# Teste.net
KiCad netlist of a schematic drawn in EAGLE
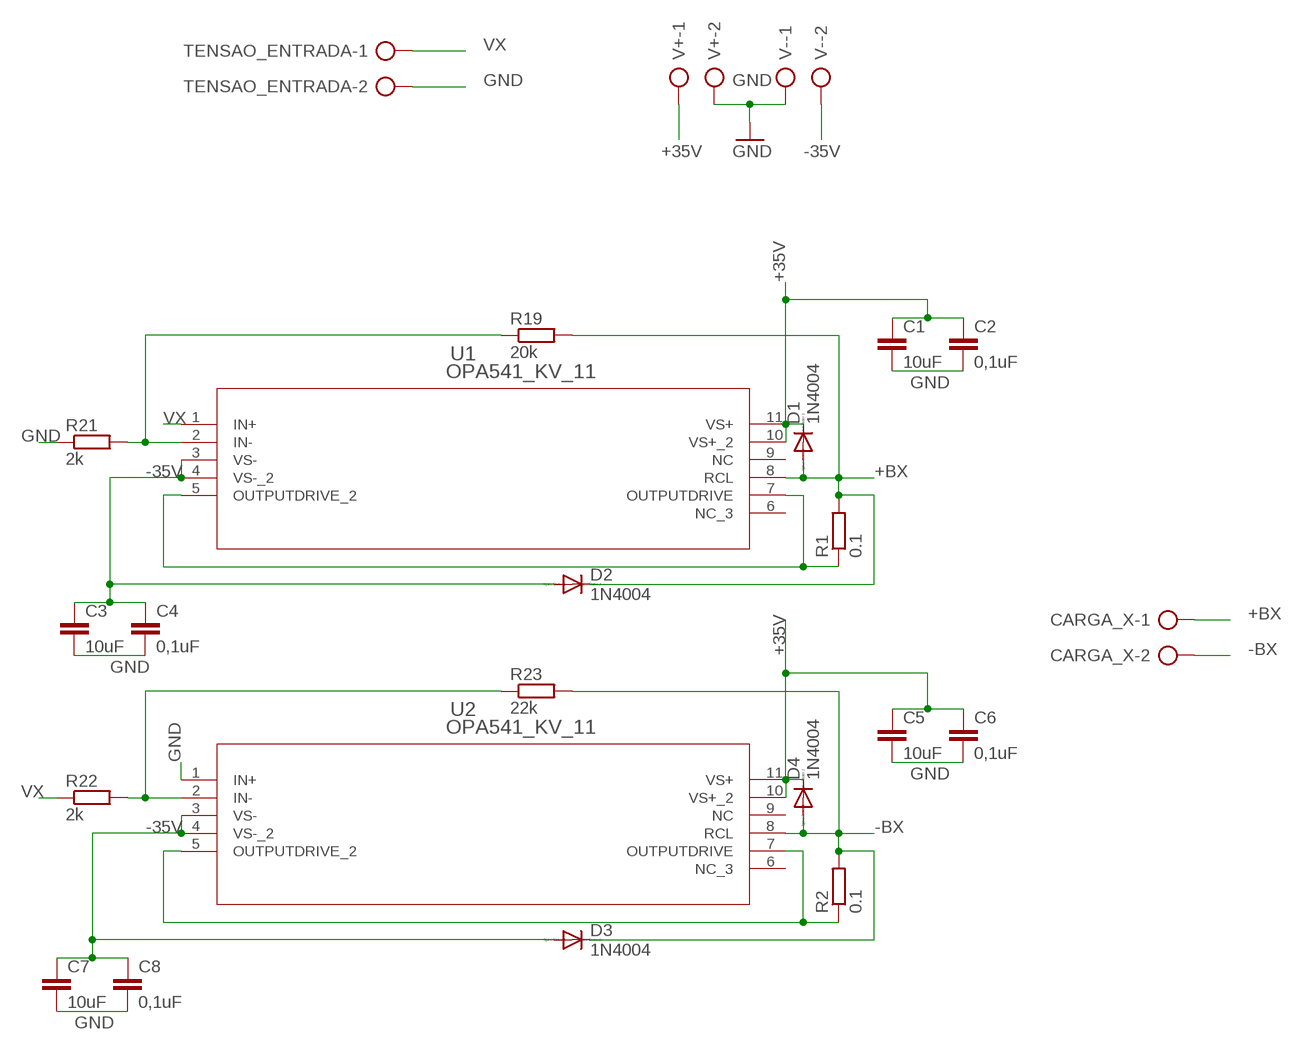
[diagram p0: schematic, sheet 1]

(export (version "E")
  (design (tool "Eeschema 10.0.6"))
  (components
    (comp (ref "C1")
      (value "10uF")
      (footprint "eagle-import:C025-024X044")
      (libsource (lib "eagle-import") (part "C-EU025-024X044"))
    )
    (comp (ref "C2")
      (value "0,1uF")
      (footprint "eagle-import:C025-024X044")
      (libsource (lib "eagle-import") (part "C-EU025-024X044"))
    )
    (comp (ref "C3")
      (value "10uF")
      (footprint "eagle-import:C025-024X044")
      (libsource (lib "eagle-import") (part "C-EU025-024X044"))
    )
    (comp (ref "C4")
      (value "0,1uF")
      (footprint "eagle-import:C025-024X044")
      (libsource (lib "eagle-import") (part "C-EU025-024X044"))
    )
    (comp (ref "C5")
      (value "10uF")
      (footprint "eagle-import:C025-024X044")
      (libsource (lib "eagle-import") (part "C-EU025-024X044"))
    )
    (comp (ref "C6")
      (value "0,1uF")
      (footprint "eagle-import:C025-024X044")
      (libsource (lib "eagle-import") (part "C-EU025-024X044"))
    )
    (comp (ref "C7")
      (value "10uF")
      (footprint "eagle-import:C025-024X044")
      (libsource (lib "eagle-import") (part "C-EU025-024X044"))
    )
    (comp (ref "C8")
      (value "0,1uF")
      (footprint "eagle-import:C025-024X044")
      (libsource (lib "eagle-import") (part "C-EU025-024X044"))
    )
    (comp (ref "CARGA_X")
      (value "AK500/2-H")
      (footprint "eagle-import:AK500_2-H")
      (libsource (lib "eagle-import") (part "AK500/2-H"))
    )
    (comp (ref "D1")
      (value "1N4004")
      (footprint "eagle-import:DO41-10")
      (libsource (lib "eagle-import") (part "1N4004"))
    )
    (comp (ref "D2")
      (value "1N4004")
      (footprint "eagle-import:DO41-10")
      (libsource (lib "eagle-import") (part "1N4004"))
    )
    (comp (ref "D3")
      (value "1N4004")
      (footprint "eagle-import:DO41-10")
      (libsource (lib "eagle-import") (part "1N4004"))
    )
    (comp (ref "D4")
      (value "1N4004")
      (footprint "eagle-import:DO41-10")
      (libsource (lib "eagle-import") (part "1N4004"))
    )
    (comp (ref "R1")
      (value "0.1")
      (footprint "eagle-import:0204_7")
      (libsource (lib "eagle-import") (part "R-EU_0204/7"))
    )
    (comp (ref "R2")
      (value "0.1")
      (footprint "eagle-import:0204_7")
      (libsource (lib "eagle-import") (part "R-EU_0204/7"))
    )
    (comp (ref "R19")
      (value "20k")
      (footprint "eagle-import:0207_7")
      (libsource (lib "eagle-import") (part "R-EU_0207/7"))
    )
    (comp (ref "R21")
      (value "2k")
      (footprint "eagle-import:0207_7")
      (libsource (lib "eagle-import") (part "R-EU_0207/7"))
    )
    (comp (ref "R22")
      (value "2k")
      (footprint "eagle-import:0207_7")
      (libsource (lib "eagle-import") (part "R-EU_0207/7"))
    )
    (comp (ref "R23")
      (value "22k")
      (footprint "eagle-import:0207_7")
      (libsource (lib "eagle-import") (part "R-EU_0207/7"))
    )
    (comp (ref "TENSAO_ENTRADA")
      (value "AK500/2-H")
      (footprint "eagle-import:AK500_2-H")
      (libsource (lib "eagle-import") (part "AK500/2-H"))
    )
    (comp (ref "U1")
      (value "OPA541_KV_11")
      (footprint "eagle-import:KV11")
      (fields (field (name "MANUFACTURER_PART_NUMBER") "opa541_kv_11"))
      (libsource (lib "eagle-import") (part "OPA541_KV_11"))
    )
    (comp (ref "U2")
      (value "OPA541_KV_11")
      (footprint "eagle-import:KV11")
      (fields (field (name "MANUFACTURER_PART_NUMBER") "opa541_kv_11"))
      (libsource (lib "eagle-import") (part "OPA541_KV_11"))
    )
    (comp (ref "V+")
      (value "AK500/2-H")
      (footprint "eagle-import:AK500_2-H")
      (libsource (lib "eagle-import") (part "AK500/2-H"))
    )
    (comp (ref "V-")
      (value "AK500/2-H")
      (footprint "eagle-import:AK500_2-H")
      (libsource (lib "eagle-import") (part "AK500/2-H"))
    )
  )
  (nets
    (net (code "1") (name "/+35V") (class "Default")
      (node (ref "C1") (pin "1") (pinfunction "1_1") (pintype "passive"))
      (node (ref "C2") (pin "1") (pinfunction "1_1") (pintype "passive"))
      (node (ref "C5") (pin "1") (pinfunction "1_1") (pintype "passive"))
      (node (ref "C6") (pin "1") (pinfunction "1_1") (pintype "passive"))
      (node (ref "D1") (pin "C") (pinfunction "C_C") (pintype "passive"))
      (node (ref "D4") (pin "C") (pinfunction "C_C") (pintype "passive"))
      (node (ref "U1") (pin "10") (pinfunction "VS+_2_10") (pintype "power_in"))
      (node (ref "U1") (pin "11") (pinfunction "VS+_11") (pintype "power_in"))
      (node (ref "U2") (pin "10") (pinfunction "VS+_2_10") (pintype "power_in"))
      (node (ref "U2") (pin "11") (pinfunction "VS+_11") (pintype "power_in"))
      (node (ref "V+") (pin "1") (pinfunction "KL_1") (pintype "passive"))
    )
    (net (code "2") (name "/+BX") (class "Default")
      (node (ref "CARGA_X") (pin "1") (pinfunction "KL_1") (pintype "passive"))
      (node (ref "D1") (pin "A") (pinfunction "A_A") (pintype "passive"))
      (node (ref "D2") (pin "C") (pinfunction "C_C") (pintype "passive"))
      (node (ref "R1") (pin "2") (pinfunction "2_2") (pintype "passive"))
      (node (ref "R19") (pin "2") (pinfunction "2_2") (pintype "passive"))
      (node (ref "U1") (pin "8") (pinfunction "RCL_8") (pintype "output"))
    )
    (net (code "3") (name "/-35V") (class "Default")
      (node (ref "C3") (pin "1") (pinfunction "1_1") (pintype "passive"))
      (node (ref "C4") (pin "1") (pinfunction "1_1") (pintype "passive"))
      (node (ref "C7") (pin "1") (pinfunction "1_1") (pintype "passive"))
      (node (ref "C8") (pin "1") (pinfunction "1_1") (pintype "passive"))
      (node (ref "D2") (pin "A") (pinfunction "A_A") (pintype "passive"))
      (node (ref "D3") (pin "A") (pinfunction "A_A") (pintype "passive"))
      (node (ref "U1") (pin "3") (pinfunction "VS-_3") (pintype "power_in"))
      (node (ref "U1") (pin "4") (pinfunction "VS-_2_4") (pintype "power_in"))
      (node (ref "U2") (pin "3") (pinfunction "VS-_3") (pintype "power_in"))
      (node (ref "U2") (pin "4") (pinfunction "VS-_2_4") (pintype "power_in"))
      (node (ref "V-") (pin "2") (pinfunction "KL_2") (pintype "passive"))
    )
    (net (code "4") (name "/-BX") (class "Default")
      (node (ref "CARGA_X") (pin "2") (pinfunction "KL_2") (pintype "passive"))
      (node (ref "D3") (pin "C") (pinfunction "C_C") (pintype "passive"))
      (node (ref "D4") (pin "A") (pinfunction "A_A") (pintype "passive"))
      (node (ref "R2") (pin "2") (pinfunction "2_2") (pintype "passive"))
      (node (ref "R23") (pin "2") (pinfunction "2_2") (pintype "passive"))
      (node (ref "U2") (pin "8") (pinfunction "RCL_8") (pintype "output"))
    )
    (net (code "5") (name "/VX") (class "Default")
      (node (ref "R22") (pin "1") (pinfunction "1_1") (pintype "passive"))
      (node (ref "TENSAO_ENTRADA") (pin "1") (pinfunction "KL_1") (pintype "passive"))
      (node (ref "U1") (pin "1") (pinfunction "IN+_1") (pintype "input"))
    )
    (net (code "6") (name "GND") (class "Default")
      (node (ref "C1") (pin "2") (pinfunction "2_2") (pintype "passive"))
      (node (ref "C2") (pin "2") (pinfunction "2_2") (pintype "passive"))
      (node (ref "C3") (pin "2") (pinfunction "2_2") (pintype "passive"))
      (node (ref "C4") (pin "2") (pinfunction "2_2") (pintype "passive"))
      (node (ref "C5") (pin "2") (pinfunction "2_2") (pintype "passive"))
      (node (ref "C6") (pin "2") (pinfunction "2_2") (pintype "passive"))
      (node (ref "C7") (pin "2") (pinfunction "2_2") (pintype "passive"))
      (node (ref "C8") (pin "2") (pinfunction "2_2") (pintype "passive"))
      (node (ref "R21") (pin "1") (pinfunction "1_1") (pintype "passive"))
      (node (ref "TENSAO_ENTRADA") (pin "2") (pinfunction "KL_2") (pintype "passive"))
      (node (ref "U2") (pin "1") (pinfunction "IN+_1") (pintype "input"))
      (node (ref "V+") (pin "2") (pinfunction "KL_2") (pintype "passive"))
      (node (ref "V-") (pin "1") (pinfunction "KL_1") (pintype "passive"))
    )
    (net (code "7") (name "Net-(U1-IN-)") (class "Default")
      (node (ref "R19") (pin "1") (pinfunction "1_1") (pintype "passive"))
      (node (ref "R21") (pin "2") (pinfunction "2_2") (pintype "passive"))
      (node (ref "U1") (pin "2") (pinfunction "IN-_2") (pintype "input"))
    )
    (net (code "8") (name "Net-(U1-OUTPUTDRIVE)") (class "Default")
      (node (ref "R1") (pin "1") (pinfunction "1_1") (pintype "passive"))
      (node (ref "U1") (pin "5") (pinfunction "OUTPUTDRIVE_2_5") (pintype "output"))
      (node (ref "U1") (pin "7") (pinfunction "OUTPUTDRIVE_7") (pintype "output"))
    )
    (net (code "9") (name "Net-(U2-IN-)") (class "Default")
      (node (ref "R22") (pin "2") (pinfunction "2_2") (pintype "passive"))
      (node (ref "R23") (pin "1") (pinfunction "1_1") (pintype "passive"))
      (node (ref "U2") (pin "2") (pinfunction "IN-_2") (pintype "input"))
    )
    (net (code "10") (name "Net-(U2-OUTPUTDRIVE)") (class "Default")
      (node (ref "R2") (pin "1") (pinfunction "1_1") (pintype "passive"))
      (node (ref "U2") (pin "5") (pinfunction "OUTPUTDRIVE_2_5") (pintype "output"))
      (node (ref "U2") (pin "7") (pinfunction "OUTPUTDRIVE_7") (pintype "output"))
    )
    (net (code "11") (name "unconnected-(U1-NC-Pad9)") (class "Default")
      (node (ref "U1") (pin "9") (pinfunction "NC_9") (pintype "passive"))
    )
    (net (code "12") (name "unconnected-(U1-NC_3-Pad6)") (class "Default")
      (node (ref "U1") (pin "6") (pinfunction "NC_3_6") (pintype "passive"))
    )
    (net (code "13") (name "unconnected-(U2-NC-Pad9)") (class "Default")
      (node (ref "U2") (pin "9") (pinfunction "NC_9") (pintype "passive"))
    )
    (net (code "14") (name "unconnected-(U2-NC_3-Pad6)") (class "Default")
      (node (ref "U2") (pin "6") (pinfunction "NC_3_6") (pintype "passive"))
    )
  )
)
